# Main-v1_0.net
KiCad netlist of a schematic drawn in EAGLE
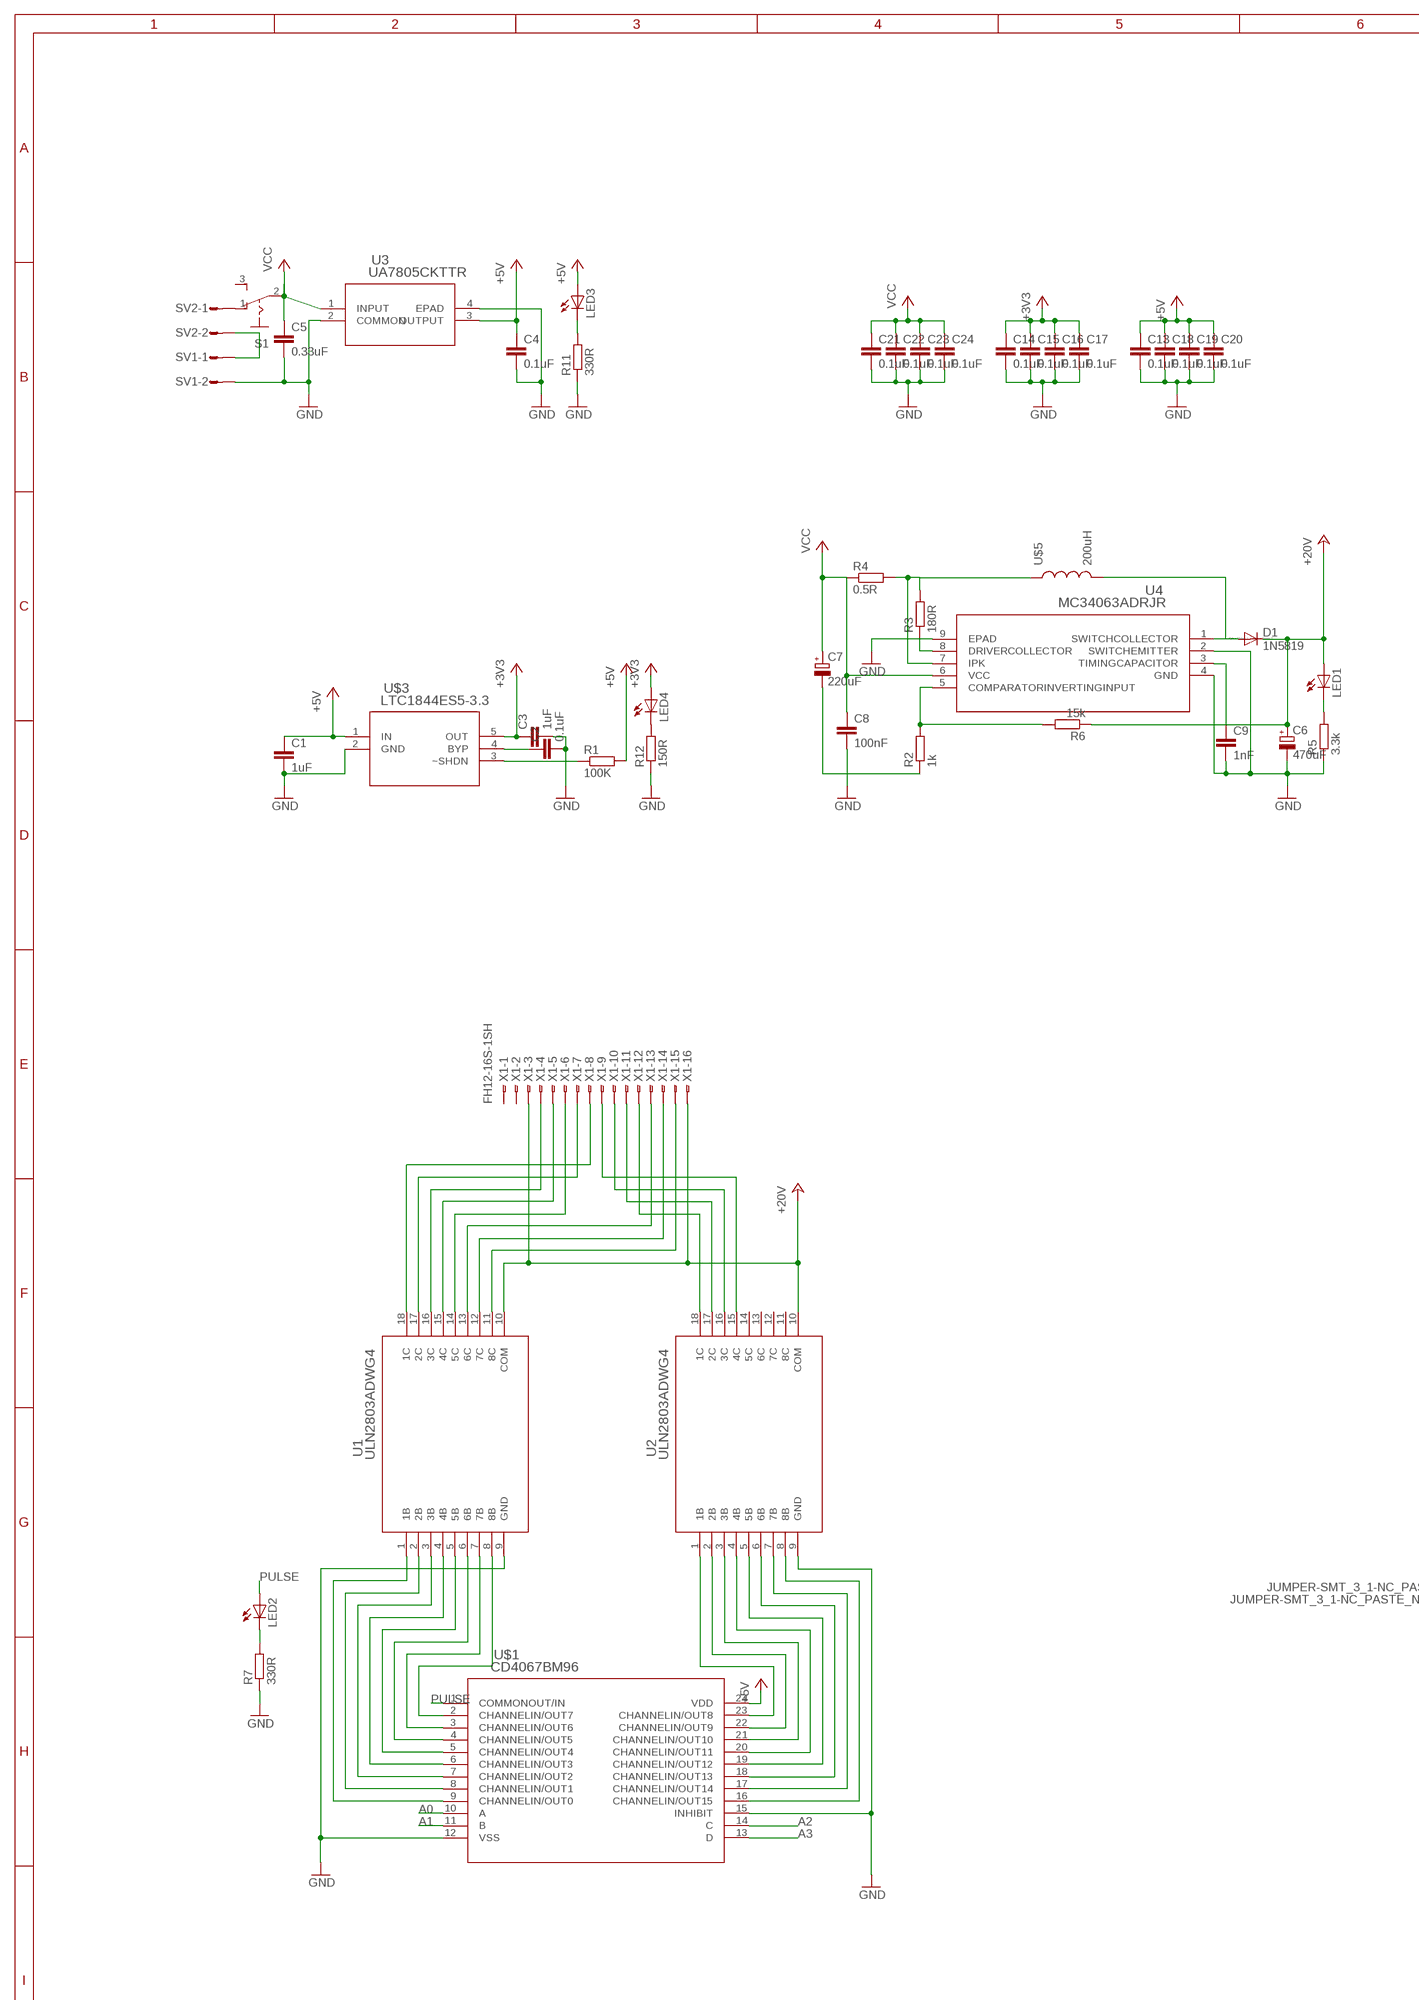
[diagram p0: schematic, sheet 1, part 1 of 2]
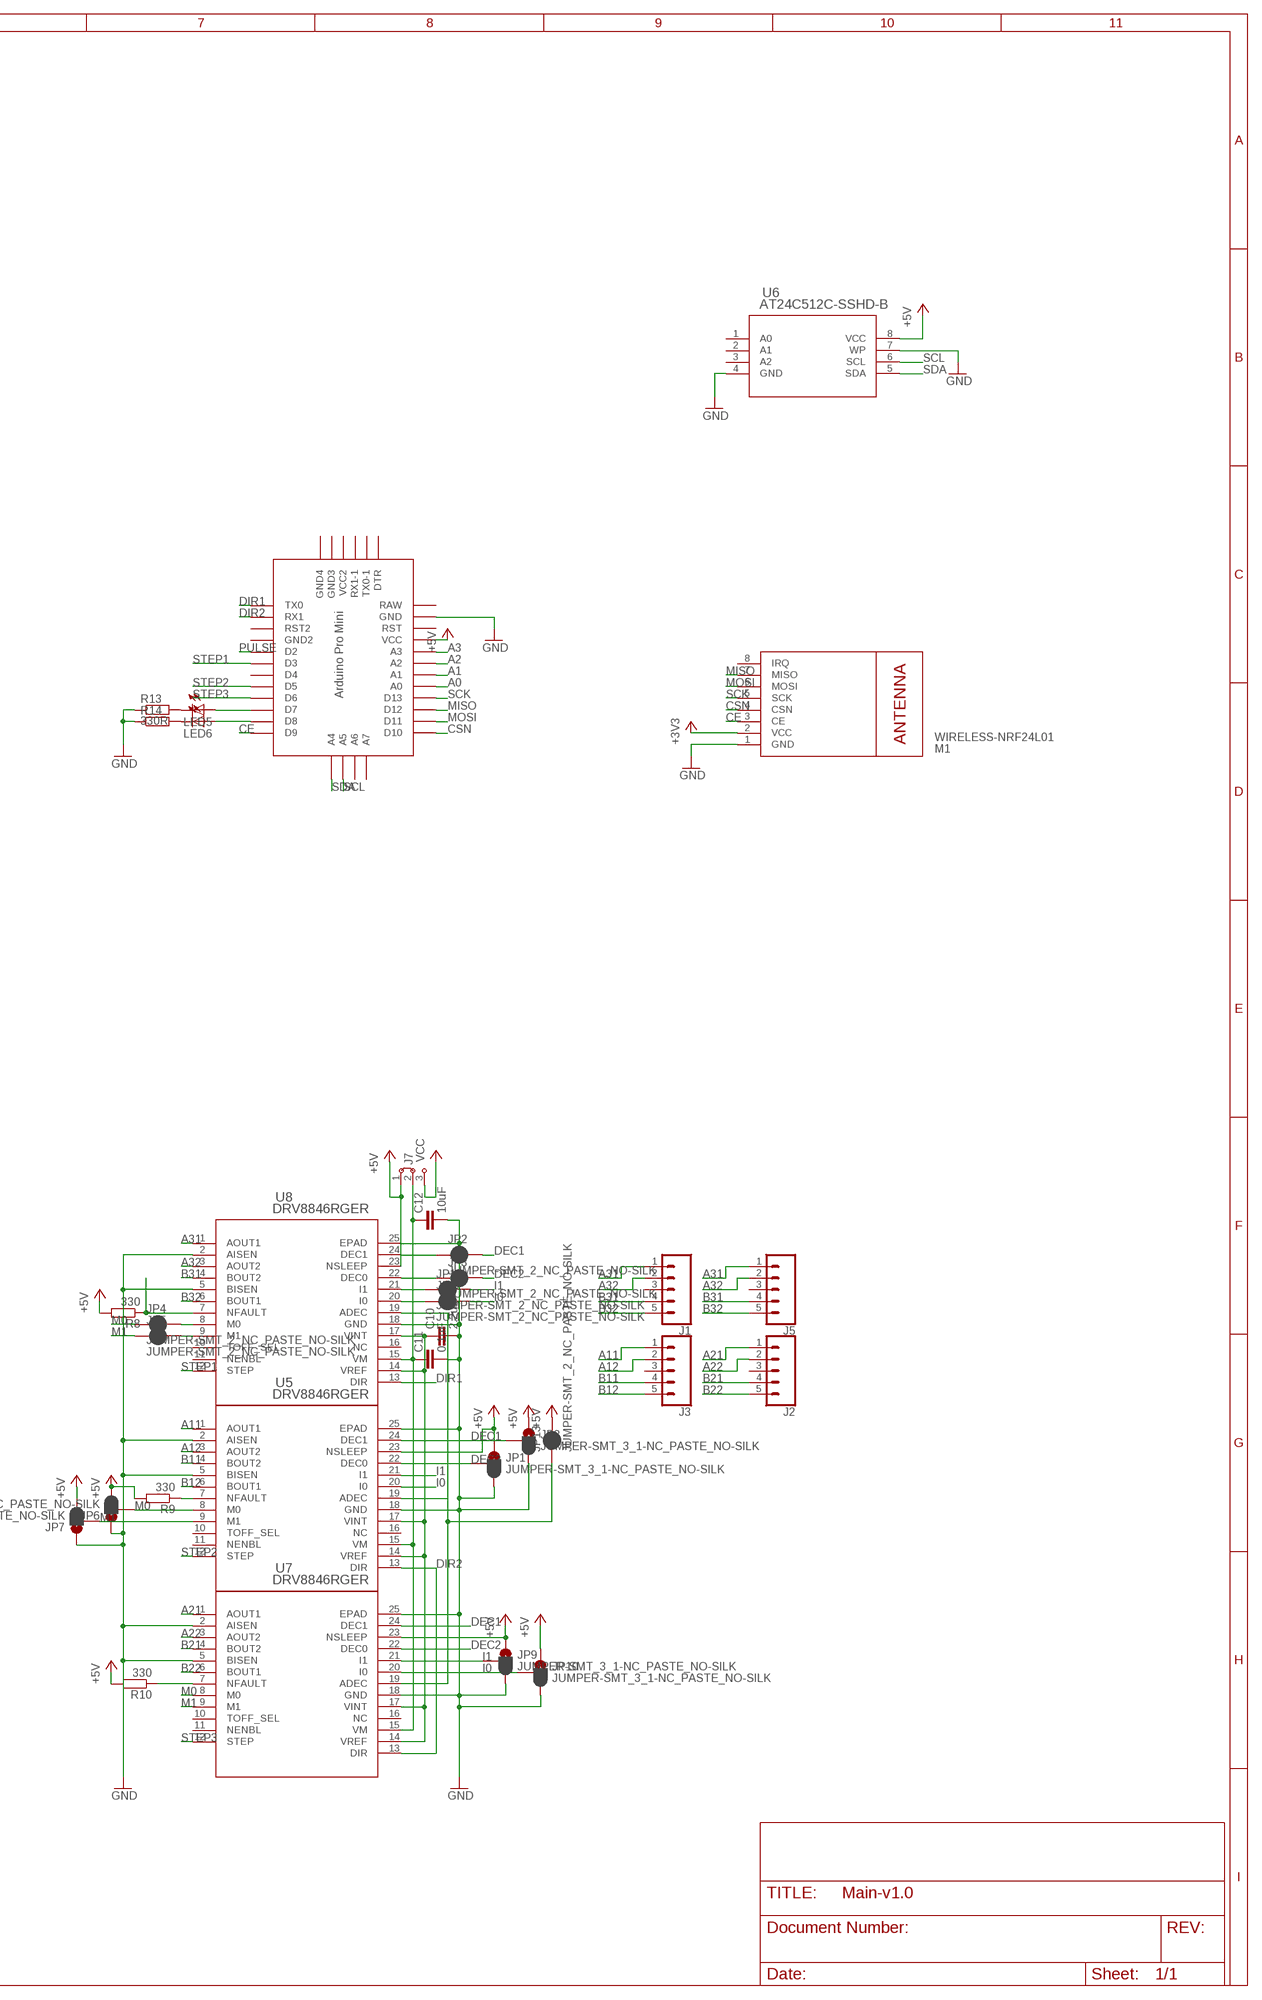
[diagram p1: schematic, sheet 1, part 2 of 2]

(export (version "E")
  (design (tool "Eeschema 10.0.6"))
  (components
    (comp (ref "C1")
      (value "1uF")
      (footprint "eagle-import:C0603")
      (libsource (lib "eagle-import") (part "resistor_C-EUC0603"))
    )
    (comp (ref "C2")
      (value "0.1uF")
      (footprint "eagle-import:C0603")
      (libsource (lib "eagle-import") (part "resistor_C-EUC0603"))
    )
    (comp (ref "C3")
      (value "1uF")
      (footprint "eagle-import:C0603")
      (libsource (lib "eagle-import") (part "resistor_C-EUC0603"))
    )
    (comp (ref "C4")
      (value "0.1uF")
      (footprint "eagle-import:C0603")
      (libsource (lib "eagle-import") (part "resistor_C-EUC0603"))
    )
    (comp (ref "C5")
      (value "0.33uF")
      (footprint "eagle-import:C0603")
      (libsource (lib "eagle-import") (part "resistor_C-EUC0603"))
    )
    (comp (ref "C6")
      (value "470uF")
      (footprint "eagle-import:153CLV-1010")
      (libsource (lib "eagle-import") (part "resistor_CPOL-EU153CLV-1010"))
    )
    (comp (ref "C7")
      (value "220uF")
      (footprint "eagle-import:SMC_C")
      (libsource (lib "eagle-import") (part "CPOL-EUSMCC"))
    )
    (comp (ref "C8")
      (value "100nF")
      (footprint "eagle-import:C0603")
      (libsource (lib "eagle-import") (part "C-EUC0603"))
    )
    (comp (ref "C9")
      (value "1nF")
      (footprint "eagle-import:C0603")
      (libsource (lib "eagle-import") (part "C-EUC0603"))
    )
    (comp (ref "C10")
      (value "2.2uF")
      (footprint "eagle-import:C0603")
      (libsource (lib "eagle-import") (part "resistor_348_C-EUC0603"))
    )
    (comp (ref "C11")
      (value "0.1uF")
      (footprint "eagle-import:C0603")
      (libsource (lib "eagle-import") (part "resistor_348_C-EUC0603"))
    )
    (comp (ref "C12")
      (value "10uF")
      (footprint "eagle-import:C0603")
      (libsource (lib "eagle-import") (part "resistor_348_C-EUC0603"))
    )
    (comp (ref "C13")
      (value "0.1uF")
      (footprint "eagle-import:C0603")
      (libsource (lib "eagle-import") (part "resistor_C-EUC0603"))
    )
    (comp (ref "C14")
      (value "0.1uF")
      (footprint "eagle-import:C0603")
      (libsource (lib "eagle-import") (part "resistor_C-EUC0603"))
    )
    (comp (ref "C15")
      (value "0.1uF")
      (footprint "eagle-import:C0603")
      (libsource (lib "eagle-import") (part "resistor_C-EUC0603"))
    )
    (comp (ref "C16")
      (value "0.1uF")
      (footprint "eagle-import:C0603")
      (libsource (lib "eagle-import") (part "resistor_C-EUC0603"))
    )
    (comp (ref "C17")
      (value "0.1uF")
      (footprint "eagle-import:C0603")
      (libsource (lib "eagle-import") (part "resistor_C-EUC0603"))
    )
    (comp (ref "C18")
      (value "0.1uF")
      (footprint "eagle-import:C0603")
      (libsource (lib "eagle-import") (part "resistor_C-EUC0603"))
    )
    (comp (ref "C19")
      (value "0.1uF")
      (footprint "eagle-import:C0603")
      (libsource (lib "eagle-import") (part "resistor_C-EUC0603"))
    )
    (comp (ref "C20")
      (value "0.1uF")
      (footprint "eagle-import:C0603")
      (libsource (lib "eagle-import") (part "resistor_C-EUC0603"))
    )
    (comp (ref "C21")
      (value "0.1uF")
      (footprint "eagle-import:C0603")
      (libsource (lib "eagle-import") (part "resistor_C-EUC0603"))
    )
    (comp (ref "C22")
      (value "0.1uF")
      (footprint "eagle-import:C0603")
      (libsource (lib "eagle-import") (part "resistor_C-EUC0603"))
    )
    (comp (ref "C23")
      (value "0.1uF")
      (footprint "eagle-import:C0603")
      (libsource (lib "eagle-import") (part "resistor_C-EUC0603"))
    )
    (comp (ref "C24")
      (value "0.1uF")
      (footprint "eagle-import:C0603")
      (libsource (lib "eagle-import") (part "resistor_C-EUC0603"))
    )
    (comp (ref "D1")
      (value "1N5819")
      (footprint "eagle-import:SOD123")
      (libsource (lib "eagle-import") (part "1N5819"))
    )
    (comp (ref "J1")
      (value "CONN_05JST-VERT")
      (footprint "eagle-import:JST-5-PTH-VERT")
      (libsource (lib "eagle-import") (part "CONN_05JST-VERT"))
    )
    (comp (ref "J2")
      (value "CONN_05JST-VERT")
      (footprint "eagle-import:JST-5-PTH-VERT")
      (libsource (lib "eagle-import") (part "CONN_05JST-VERT"))
    )
    (comp (ref "J3")
      (value "CONN_05JST-VERT")
      (footprint "eagle-import:JST-5-PTH-VERT")
      (libsource (lib "eagle-import") (part "CONN_05JST-VERT"))
    )
    (comp (ref "J5")
      (value "CONN_05JST-VERT")
      (footprint "eagle-import:JST-5-PTH-VERT")
      (libsource (lib "eagle-import") (part "CONN_05JST-VERT"))
    )
    (comp (ref "J7")
      (value "J2X2MM")
      (footprint "eagle-import:04C")
      (libsource (lib "eagle-import") (part "J2X2MM"))
    )
    (comp (ref "JP1")
      (value "JUMPER-SMT_3_1-NC_PASTE_NO-SILK")
      (footprint "eagle-import:SMT-JUMPER_3_1-NC_PASTE_NO-SILK")
      (libsource (lib "eagle-import") (part "JUMPER-SMT_3_1-NC_PASTE_NO-SILK"))
    )
    (comp (ref "JP2")
      (value "JUMPER-SMT_2_NC_PASTE_NO-SILK")
      (footprint "eagle-import:SMT-JUMPER_2_NC_PASTE_NO-SILK")
      (libsource (lib "eagle-import") (part "JUMPER-SMT_2_NC_PASTE_NO-SILK"))
    )
    (comp (ref "JP3")
      (value "JUMPER-SMT_2_NC_PASTE_NO-SILK")
      (footprint "eagle-import:SMT-JUMPER_2_NC_PASTE_NO-SILK")
      (libsource (lib "eagle-import") (part "JUMPER-SMT_2_NC_PASTE_NO-SILK"))
    )
    (comp (ref "JP4")
      (value "JUMPER-SMT_2_NC_PASTE_NO-SILK")
      (footprint "eagle-import:SMT-JUMPER_2_NC_PASTE_NO-SILK")
      (libsource (lib "eagle-import") (part "JUMPER-SMT_2_NC_PASTE_NO-SILK"))
    )
    (comp (ref "JP5")
      (value "JUMPER-SMT_2_NC_PASTE_NO-SILK")
      (footprint "eagle-import:SMT-JUMPER_2_NC_PASTE_NO-SILK")
      (libsource (lib "eagle-import") (part "JUMPER-SMT_2_NC_PASTE_NO-SILK"))
    )
    (comp (ref "JP6")
      (value "JUMPER-SMT_3_1-NC_PASTE_NO-SILK")
      (footprint "eagle-import:SMT-JUMPER_3_1-NC_PASTE_NO-SILK")
      (libsource (lib "eagle-import") (part "JUMPER-SMT_3_1-NC_PASTE_NO-SILK"))
    )
    (comp (ref "JP7")
      (value "JUMPER-SMT_3_1-NC_PASTE_NO-SILK")
      (footprint "eagle-import:SMT-JUMPER_3_1-NC_PASTE_NO-SILK")
      (libsource (lib "eagle-import") (part "JUMPER-SMT_3_1-NC_PASTE_NO-SILK"))
    )
    (comp (ref "JP8")
      (value "JUMPER-SMT_3_1-NC_PASTE_NO-SILK")
      (footprint "eagle-import:SMT-JUMPER_3_1-NC_PASTE_NO-SILK")
      (libsource (lib "eagle-import") (part "JUMPER-SMT_3_1-NC_PASTE_NO-SILK"))
    )
    (comp (ref "JP9")
      (value "JUMPER-SMT_3_1-NC_PASTE_NO-SILK")
      (footprint "eagle-import:SMT-JUMPER_3_1-NC_PASTE_NO-SILK")
      (libsource (lib "eagle-import") (part "JUMPER-SMT_3_1-NC_PASTE_NO-SILK"))
    )
    (comp (ref "JP10")
      (value "JUMPER-SMT_3_1-NC_PASTE_NO-SILK")
      (footprint "eagle-import:SMT-JUMPER_3_1-NC_PASTE_NO-SILK")
      (libsource (lib "eagle-import") (part "JUMPER-SMT_3_1-NC_PASTE_NO-SILK"))
    )
    (comp (ref "JP11")
      (value "JUMPER-SMT_2_NC_PASTE_NO-SILK")
      (footprint "eagle-import:SMT-JUMPER_2_NC_PASTE_NO-SILK")
      (libsource (lib "eagle-import") (part "JUMPER-SMT_2_NC_PASTE_NO-SILK"))
    )
    (comp (ref "JP12")
      (value "JUMPER-SMT_2_NC_PASTE_NO-SILK")
      (footprint "eagle-import:SMT-JUMPER_2_NC_PASTE_NO-SILK")
      (libsource (lib "eagle-import") (part "JUMPER-SMT_2_NC_PASTE_NO-SILK"))
    )
    (comp (ref "JP13")
      (value "JUMPER-SMT_2_NC_PASTE_NO-SILK")
      (footprint "eagle-import:SMT-JUMPER_2_NC_PASTE_NO-SILK")
      (libsource (lib "eagle-import") (part "JUMPER-SMT_2_NC_PASTE_NO-SILK"))
    )
    (comp (ref "LED1")
      (value "LEDSML0603")
      (footprint "eagle-import:SML0603")
      (libsource (lib "eagle-import") (part "LEDSML0603"))
    )
    (comp (ref "LED2")
      (value "LEDSML0603")
      (footprint "eagle-import:SML0603")
      (libsource (lib "eagle-import") (part "LEDSML0603"))
    )
    (comp (ref "LED3")
      (value "LEDSML0603")
      (footprint "eagle-import:SML0603")
      (libsource (lib "eagle-import") (part "LEDSML0603"))
    )
    (comp (ref "LED4")
      (value "LEDSML0603")
      (footprint "eagle-import:SML0603")
      (libsource (lib "eagle-import") (part "LEDSML0603"))
    )
    (comp (ref "LED5")
      (value "LEDSML0603")
      (footprint "eagle-import:SML0603")
      (libsource (lib "eagle-import") (part "LEDSML0603"))
    )
    (comp (ref "LED6")
      (value "LEDSML0603")
      (footprint "eagle-import:SML0603")
      (libsource (lib "eagle-import") (part "LEDSML0603"))
    )
    (comp (ref "M1")
      (value "WIRELESS-NRF24L01")
      (footprint "eagle-import:WIRELESS-NRF24L01")
      (libsource (lib "eagle-import") (part "WIRELESS-NRF24L01"))
    )
    (comp (ref "R1")
      (value "100K")
      (footprint "eagle-import:R0603")
      (libsource (lib "eagle-import") (part "R-EU_R0603"))
    )
    (comp (ref "R2")
      (value "1k")
      (footprint "eagle-import:R0603")
      (libsource (lib "eagle-import") (part "R-EU_R0603"))
    )
    (comp (ref "R3")
      (value "180R")
      (footprint "eagle-import:R0603")
      (libsource (lib "eagle-import") (part "R-EU_R0603"))
    )
    (comp (ref "R4")
      (value "0.5R")
      (footprint "eagle-import:R0603")
      (libsource (lib "eagle-import") (part "R-EU_R0603"))
    )
    (comp (ref "R5")
      (value "3.3k")
      (footprint "eagle-import:R0603")
      (libsource (lib "eagle-import") (part "R-EU_R0603"))
    )
    (comp (ref "R6")
      (value "15k")
      (footprint "eagle-import:R0603")
      (libsource (lib "eagle-import") (part "R-EU_R0603"))
    )
    (comp (ref "R7")
      (value "330R")
      (footprint "eagle-import:R0603")
      (libsource (lib "eagle-import") (part "R-EU_R0603"))
    )
    (comp (ref "R8")
      (value "330")
      (footprint "eagle-import:R0603")
      (libsource (lib "eagle-import") (part "R-EU_R0603"))
    )
    (comp (ref "R9")
      (value "330")
      (footprint "eagle-import:R0603")
      (libsource (lib "eagle-import") (part "R-EU_R0603"))
    )
    (comp (ref "R10")
      (value "330")
      (footprint "eagle-import:R0603")
      (libsource (lib "eagle-import") (part "R-EU_R0603"))
    )
    (comp (ref "R11")
      (value "330R")
      (footprint "eagle-import:R0603")
      (libsource (lib "eagle-import") (part "R-EU_R0603"))
    )
    (comp (ref "R12")
      (value "150R")
      (footprint "eagle-import:R0603")
      (libsource (lib "eagle-import") (part "R-EU_R0603"))
    )
    (comp (ref "R13")
      (value "330R")
      (footprint "eagle-import:R0603")
      (libsource (lib "eagle-import") (part "R-EU_R0603"))
    )
    (comp (ref "R14")
      (value "R-EU_R0603")
      (footprint "eagle-import:R0603")
      (libsource (lib "eagle-import") (part "R-EU_R0603"))
    )
    (comp (ref "S1")
      (value "255SB")
      (footprint "eagle-import:255SB")
      (libsource (lib "eagle-import") (part "255SB"))
    )
    (comp (ref "SV1")
      (value "L02P")
      (footprint "eagle-import:L02P")
      (libsource (lib "eagle-import") (part "L02P"))
    )
    (comp (ref "SV2")
      (value "L02P")
      (footprint "eagle-import:L02P")
      (libsource (lib "eagle-import") (part "L02P"))
    )
    (comp (ref "U$1")
      (value "CD4067BM96")
      (footprint "eagle-import:DW24")
      (fields (field (name "MANUFACTURER_PART_NUMBER") "CD4067B_DW_24"))
      (libsource (lib "eagle-import") (part "CD4067BM96"))
    )
    (comp (ref "U$2")
      (value "PRO-MINI")
      (footprint "eagle-import:PRO-MINI")
      (libsource (lib "eagle-import") (part "PRO-MINI"))
    )
    (comp (ref "U$3")
      (value "LTC1844ES5-3.3")
      (footprint "eagle-import:TSOT-23_S5")
      (libsource (lib "eagle-import") (part "LTC1844ES5-3.3"))
    )
    (comp (ref "U$5")
      (value "200uH")
      (footprint "eagle-import:CR54")
      (libsource (lib "eagle-import") (part "INDUCTORCR54"))
    )
    (comp (ref "U1")
      (value "ULN2803ADWG4")
      (footprint "eagle-import:DW18")
      (libsource (lib "eagle-import") (part "ULN2803ADWG4"))
    )
    (comp (ref "U2")
      (value "ULN2803ADWG4")
      (footprint "eagle-import:DW18")
      (libsource (lib "eagle-import") (part "ULN2803ADWG4"))
    )
    (comp (ref "U3")
      (value "UA7805CKTTR")
      (footprint "eagle-import:KTT3_6P22X6P6")
      (libsource (lib "eagle-import") (part "UA7805CKTTR"))
    )
    (comp (ref "U4")
      (value "MC34063ADRJR")
      (footprint "eagle-import:DRJ8_2P2X3")
      (libsource (lib "eagle-import") (part "MC34063ADRJR"))
    )
    (comp (ref "U5")
      (value "DRV8846RGER")
      (footprint "eagle-import:RGE24_2P45X2P45")
      (fields (field (name "MANUFACTURER_PART_NUMBER") "drv8846rger"))
      (libsource (lib "eagle-import") (part "DRV8846RGER"))
    )
    (comp (ref "U6")
      (value "AT24C512C-SSHD-B")
      (footprint "eagle-import:8S1")
      (fields (field (name "MANUFACTURER_PART_NUMBER") "AT24C512CSSHDB"))
      (libsource (lib "eagle-import") (part "AT24C512C-SSHD-B"))
    )
    (comp (ref "U7")
      (value "DRV8846RGER")
      (footprint "eagle-import:RGE24_2P45X2P45")
      (fields (field (name "MANUFACTURER_PART_NUMBER") "drv8846rger"))
      (libsource (lib "eagle-import") (part "DRV8846RGER"))
    )
    (comp (ref "U8")
      (value "DRV8846RGER")
      (footprint "eagle-import:RGE24_2P45X2P45")
      (fields (field (name "MANUFACTURER_PART_NUMBER") "drv8846rger"))
      (libsource (lib "eagle-import") (part "DRV8846RGER"))
    )
    (comp (ref "X1")
      (value "FH12-16S-1SH")
      (footprint "eagle-import:FH12-16S-1SH")
      (libsource (lib "eagle-import") (part "FH12-16S-1SH"))
    )
  )
  (nets
    (net (code "1") (name "+3V3") (class "Default")
      (node (ref "C14") (pin "1") (pinfunction "1_1") (pintype "passive"))
      (node (ref "C15") (pin "1") (pinfunction "1_1") (pintype "passive"))
      (node (ref "C16") (pin "1") (pinfunction "1_1") (pintype "passive"))
      (node (ref "C17") (pin "1") (pinfunction "1_1") (pintype "passive"))
      (node (ref "C3") (pin "1") (pinfunction "1_1") (pintype "passive"))
      (node (ref "LED4") (pin "A") (pinfunction "A_A") (pintype "passive"))
      (node (ref "M1") (pin "2") (pinfunction "VCC_2") (pintype "power_in"))
      (node (ref "U$3") (pin "5") (pinfunction "OUT_5") (pintype "passive"))
    )
    (net (code "2") (name "+5V") (class "Default")
      (node (ref "C1") (pin "1") (pinfunction "1_1") (pintype "passive"))
      (node (ref "C13") (pin "1") (pinfunction "1_1") (pintype "passive"))
      (node (ref "C18") (pin "1") (pinfunction "1_1") (pintype "passive"))
      (node (ref "C19") (pin "1") (pinfunction "1_1") (pintype "passive"))
      (node (ref "C20") (pin "1") (pinfunction "1_1") (pintype "passive"))
      (node (ref "C4") (pin "1") (pinfunction "1_1") (pintype "passive"))
      (node (ref "J7") (pin "1") (pinfunction "1_1") (pintype "passive"))
      (node (ref "JP1") (pin "1") (pinfunction "1_1") (pintype "passive"))
      (node (ref "JP10") (pin "1") (pinfunction "1_1") (pintype "passive"))
      (node (ref "JP13") (pin "2") (pinfunction "2_2") (pintype "passive"))
      (node (ref "JP6") (pin "3") (pinfunction "3_3") (pintype "passive"))
      (node (ref "JP7") (pin "3") (pinfunction "3_3") (pintype "passive"))
      (node (ref "JP8") (pin "1") (pinfunction "1_1") (pintype "passive"))
      (node (ref "JP9") (pin "1") (pinfunction "1_1") (pintype "passive"))
      (node (ref "LED3") (pin "A") (pinfunction "A_A") (pintype "passive"))
      (node (ref "R1") (pin "2") (pinfunction "2_2") (pintype "passive"))
      (node (ref "R10") (pin "2") (pinfunction "2_2") (pintype "passive"))
      (node (ref "R8") (pin "2") (pinfunction "2_2") (pintype "passive"))
      (node (ref "R9") (pin "2") (pinfunction "2_2") (pintype "passive"))
      (node (ref "U$1") (pin "24") (pinfunction "VDD_24") (pintype "power_in"))
      (node (ref "U$2") (pin "VCC") (pinfunction "VCC_VCC") (pintype "bidirectional"))
      (node (ref "U$3") (pin "1") (pinfunction "IN_1") (pintype "passive"))
      (node (ref "U3") (pin "3") (pinfunction "OUTPUT_3") (pintype "output"))
      (node (ref "U5") (pin "23") (pinfunction "NSLEEP_23") (pintype "input"))
      (node (ref "U6") (pin "8") (pinfunction "VCC_8") (pintype "power_in"))
      (node (ref "U7") (pin "23") (pinfunction "NSLEEP_23") (pintype "input"))
      (node (ref "U8") (pin "23") (pinfunction "NSLEEP_23") (pintype "input"))
    )
    (net (code "3") (name "+20V") (class "Default")
      (node (ref "C6") (pin "+") (pinfunction "+_+") (pintype "passive"))
      (node (ref "D1") (pin "C") (pinfunction "C_C") (pintype "passive"))
      (node (ref "LED1") (pin "A") (pinfunction "A_A") (pintype "passive"))
      (node (ref "R6") (pin "1") (pinfunction "1_1") (pintype "passive"))
      (node (ref "U1") (pin "10") (pinfunction "COM_10") (pintype "passive"))
      (node (ref "U2") (pin "10") (pinfunction "COM_10") (pintype "passive"))
      (node (ref "X1") (pin "16") (pinfunction "1_16") (pintype "passive"))
      (node (ref "X1") (pin "3") (pinfunction "1_3") (pintype "passive"))
    )
    (net (code "4") (name "/A0") (class "Default")
      (node (ref "U$1") (pin "10") (pinfunction "A_10") (pintype "passive"))
      (node (ref "U$2") (pin "A0") (pinfunction "A0_A0") (pintype "bidirectional"))
    )
    (net (code "5") (name "/A1") (class "Default")
      (node (ref "U$1") (pin "11") (pinfunction "B_11") (pintype "passive"))
      (node (ref "U$2") (pin "A1") (pinfunction "A1_A1") (pintype "bidirectional"))
    )
    (net (code "6") (name "/A2") (class "Default")
      (node (ref "U$1") (pin "14") (pinfunction "C_14") (pintype "passive"))
      (node (ref "U$2") (pin "A2") (pinfunction "A2_A2") (pintype "bidirectional"))
    )
    (net (code "7") (name "/A3") (class "Default")
      (node (ref "U$1") (pin "13") (pinfunction "D_13") (pintype "passive"))
      (node (ref "U$2") (pin "A3") (pinfunction "A3_A3") (pintype "bidirectional"))
    )
    (net (code "8") (name "/A11") (class "Default")
      (node (ref "J3") (pin "1") (pinfunction "1_1") (pintype "passive"))
      (node (ref "U5") (pin "1") (pinfunction "AOUT1_1") (pintype "output"))
    )
    (net (code "9") (name "/A12") (class "Default")
      (node (ref "J3") (pin "2") (pinfunction "2_2") (pintype "passive"))
      (node (ref "U5") (pin "3") (pinfunction "AOUT2_3") (pintype "output"))
    )
    (net (code "10") (name "/A21") (class "Default")
      (node (ref "J2") (pin "1") (pinfunction "1_1") (pintype "passive"))
      (node (ref "U7") (pin "1") (pinfunction "AOUT1_1") (pintype "output"))
    )
    (net (code "11") (name "/A22") (class "Default")
      (node (ref "J2") (pin "2") (pinfunction "2_2") (pintype "passive"))
      (node (ref "U7") (pin "3") (pinfunction "AOUT2_3") (pintype "output"))
    )
    (net (code "12") (name "/A31") (class "Default")
      (node (ref "J1") (pin "1") (pinfunction "1_1") (pintype "passive"))
      (node (ref "J5") (pin "1") (pinfunction "1_1") (pintype "passive"))
      (node (ref "U8") (pin "1") (pinfunction "AOUT1_1") (pintype "output"))
    )
    (net (code "13") (name "/A32") (class "Default")
      (node (ref "J1") (pin "2") (pinfunction "2_2") (pintype "passive"))
      (node (ref "J5") (pin "2") (pinfunction "2_2") (pintype "passive"))
      (node (ref "U8") (pin "3") (pinfunction "AOUT2_3") (pintype "output"))
    )
    (net (code "14") (name "/B11") (class "Default")
      (node (ref "J3") (pin "4") (pinfunction "4_4") (pintype "passive"))
      (node (ref "U5") (pin "4") (pinfunction "BOUT2_4") (pintype "output"))
    )
    (net (code "15") (name "/B12") (class "Default")
      (node (ref "J3") (pin "5") (pinfunction "5_5") (pintype "passive"))
      (node (ref "U5") (pin "6") (pinfunction "BOUT1_6") (pintype "output"))
    )
    (net (code "16") (name "/B21") (class "Default")
      (node (ref "J2") (pin "4") (pinfunction "4_4") (pintype "passive"))
      (node (ref "U7") (pin "4") (pinfunction "BOUT2_4") (pintype "output"))
    )
    (net (code "17") (name "/B22") (class "Default")
      (node (ref "J2") (pin "5") (pinfunction "5_5") (pintype "passive"))
      (node (ref "U7") (pin "6") (pinfunction "BOUT1_6") (pintype "output"))
    )
    (net (code "18") (name "/B31") (class "Default")
      (node (ref "J1") (pin "4") (pinfunction "4_4") (pintype "passive"))
      (node (ref "J5") (pin "4") (pinfunction "4_4") (pintype "passive"))
      (node (ref "U8") (pin "4") (pinfunction "BOUT2_4") (pintype "output"))
    )
    (net (code "19") (name "/B32") (class "Default")
      (node (ref "J1") (pin "5") (pinfunction "5_5") (pintype "passive"))
      (node (ref "J5") (pin "5") (pinfunction "5_5") (pintype "passive"))
      (node (ref "U8") (pin "6") (pinfunction "BOUT1_6") (pintype "output"))
    )
    (net (code "20") (name "/CE") (class "Default")
      (node (ref "M1") (pin "3") (pinfunction "CE_3") (pintype "bidirectional"))
      (node (ref "U$2") (pin "D9") (pinfunction "D9_D9") (pintype "bidirectional"))
    )
    (net (code "21") (name "/CSN") (class "Default")
      (node (ref "M1") (pin "4") (pinfunction "CSN_4") (pintype "bidirectional"))
      (node (ref "U$2") (pin "D10") (pinfunction "D10_D10") (pintype "bidirectional"))
    )
    (net (code "22") (name "/DEC1") (class "Default")
      (node (ref "JP2") (pin "2") (pinfunction "2_2") (pintype "passive"))
      (node (ref "JP8") (pin "2") (pinfunction "2_2") (pintype "passive"))
      (node (ref "U5") (pin "24") (pinfunction "DEC1_24") (pintype "input"))
      (node (ref "U7") (pin "24") (pinfunction "DEC1_24") (pintype "input"))
    )
    (net (code "23") (name "/DEC2") (class "Default")
      (node (ref "JP1") (pin "2") (pinfunction "2_2") (pintype "passive"))
      (node (ref "JP3") (pin "2") (pinfunction "2_2") (pintype "passive"))
      (node (ref "U5") (pin "22") (pinfunction "DEC0_22") (pintype "input"))
      (node (ref "U7") (pin "22") (pinfunction "DEC0_22") (pintype "input"))
    )
    (net (code "24") (name "/DIR1") (class "Default")
      (node (ref "U$2") (pin "TX0") (pinfunction "TX0_TX0") (pintype "bidirectional"))
      (node (ref "U8") (pin "13") (pinfunction "DIR_13") (pintype "input"))
    )
    (net (code "25") (name "/DIR2") (class "Default")
      (node (ref "U$2") (pin "RX1") (pinfunction "RX1_RX1") (pintype "bidirectional"))
      (node (ref "U5") (pin "13") (pinfunction "DIR_13") (pintype "input"))
      (node (ref "U7") (pin "13") (pinfunction "DIR_13") (pintype "input"))
    )
    (net (code "26") (name "/I0") (class "Default")
      (node (ref "JP10") (pin "2") (pinfunction "2_2") (pintype "passive"))
      (node (ref "JP12") (pin "2") (pinfunction "2_2") (pintype "passive"))
      (node (ref "U5") (pin "20") (pinfunction "I0_20") (pintype "input"))
      (node (ref "U7") (pin "20") (pinfunction "I0_20") (pintype "input"))
    )
    (net (code "27") (name "/I1") (class "Default")
      (node (ref "JP11") (pin "2") (pinfunction "2_2") (pintype "passive"))
      (node (ref "JP9") (pin "2") (pinfunction "2_2") (pintype "passive"))
      (node (ref "U5") (pin "21") (pinfunction "I1_21") (pintype "input"))
      (node (ref "U7") (pin "21") (pinfunction "I1_21") (pintype "input"))
    )
    (net (code "28") (name "/M0") (class "Default")
      (node (ref "JP4") (pin "1") (pinfunction "1_1") (pintype "passive"))
      (node (ref "JP6") (pin "2") (pinfunction "2_2") (pintype "passive"))
      (node (ref "U5") (pin "8") (pinfunction "M0_8") (pintype "input"))
      (node (ref "U7") (pin "8") (pinfunction "M0_8") (pintype "input"))
    )
    (net (code "29") (name "/M1") (class "Default")
      (node (ref "JP5") (pin "1") (pinfunction "1_1") (pintype "passive"))
      (node (ref "JP7") (pin "2") (pinfunction "2_2") (pintype "passive"))
      (node (ref "U5") (pin "9") (pinfunction "M1_9") (pintype "input"))
      (node (ref "U7") (pin "9") (pinfunction "M1_9") (pintype "input"))
    )
    (net (code "30") (name "/MISO") (class "Default")
      (node (ref "M1") (pin "7") (pinfunction "MISO_7") (pintype "bidirectional"))
      (node (ref "U$2") (pin "D12") (pinfunction "D12_D12") (pintype "bidirectional"))
    )
    (net (code "31") (name "/MOSI") (class "Default")
      (node (ref "M1") (pin "6") (pinfunction "MOSI_6") (pintype "bidirectional"))
      (node (ref "U$2") (pin "D11") (pinfunction "D11_D11") (pintype "bidirectional"))
    )
    (net (code "32") (name "/PULSE") (class "Default")
      (node (ref "LED2") (pin "A") (pinfunction "A_A") (pintype "passive"))
      (node (ref "U$1") (pin "1") (pinfunction "COMMONOUT/IN_1") (pintype "bidirectional"))
      (node (ref "U$2") (pin "D2") (pinfunction "D2_D2") (pintype "bidirectional"))
    )
    (net (code "33") (name "/RAW") (class "Default")
      (node (ref "U$2") (pin "RAW") (pinfunction "RAW_RAW") (pintype "power_in"))
    )
    (net (code "34") (name "/SCK") (class "Default")
      (node (ref "M1") (pin "5") (pinfunction "SCK_5") (pintype "bidirectional"))
      (node (ref "U$2") (pin "D13") (pinfunction "D13_D13") (pintype "bidirectional"))
    )
    (net (code "35") (name "/SCL") (class "Default")
      (node (ref "U$2") (pin "A5") (pinfunction "A5_A5") (pintype "bidirectional"))
      (node (ref "U6") (pin "6") (pinfunction "SCL_6") (pintype "input"))
    )
    (net (code "36") (name "/SDA") (class "Default")
      (node (ref "U$2") (pin "A4") (pinfunction "A4_A4") (pintype "bidirectional"))
      (node (ref "U6") (pin "5") (pinfunction "SDA_5") (pintype "passive"))
    )
    (net (code "37") (name "/STEP1") (class "Default")
      (node (ref "U$2") (pin "D3") (pinfunction "D3_D3") (pintype "bidirectional"))
      (node (ref "U8") (pin "12") (pinfunction "STEP_12") (pintype "input"))
    )
    (net (code "38") (name "/STEP2") (class "Default")
      (node (ref "U$2") (pin "D5") (pinfunction "D5_D5") (pintype "bidirectional"))
      (node (ref "U5") (pin "12") (pinfunction "STEP_12") (pintype "input"))
    )
    (net (code "39") (name "/STEP3") (class "Default")
      (node (ref "U$2") (pin "D6") (pinfunction "D6_D6") (pintype "bidirectional"))
      (node (ref "U7") (pin "12") (pinfunction "STEP_12") (pintype "input"))
    )
    (net (code "40") (name "GND") (class "Default")
      (node (ref "C1") (pin "2") (pinfunction "2_2") (pintype "passive"))
      (node (ref "C10") (pin "2") (pinfunction "2_2") (pintype "passive"))
      (node (ref "C11") (pin "2") (pinfunction "2_2") (pintype "passive"))
      (node (ref "C12") (pin "2") (pinfunction "2_2") (pintype "passive"))
      (node (ref "C13") (pin "2") (pinfunction "2_2") (pintype "passive"))
      (node (ref "C14") (pin "2") (pinfunction "2_2") (pintype "passive"))
      (node (ref "C15") (pin "2") (pinfunction "2_2") (pintype "passive"))
      (node (ref "C16") (pin "2") (pinfunction "2_2") (pintype "passive"))
      (node (ref "C17") (pin "2") (pinfunction "2_2") (pintype "passive"))
      (node (ref "C18") (pin "2") (pinfunction "2_2") (pintype "passive"))
      (node (ref "C19") (pin "2") (pinfunction "2_2") (pintype "passive"))
      (node (ref "C2") (pin "2") (pinfunction "2_2") (pintype "passive"))
      (node (ref "C20") (pin "2") (pinfunction "2_2") (pintype "passive"))
      (node (ref "C21") (pin "2") (pinfunction "2_2") (pintype "passive"))
      (node (ref "C22") (pin "2") (pinfunction "2_2") (pintype "passive"))
      (node (ref "C23") (pin "2") (pinfunction "2_2") (pintype "passive"))
      (node (ref "C24") (pin "2") (pinfunction "2_2") (pintype "passive"))
      (node (ref "C3") (pin "2") (pinfunction "2_2") (pintype "passive"))
      (node (ref "C4") (pin "2") (pinfunction "2_2") (pintype "passive"))
      (node (ref "C5") (pin "2") (pinfunction "2_2") (pintype "passive"))
      (node (ref "C6") (pin "-") (pinfunction "-_-") (pintype "passive"))
      (node (ref "C7") (pin "-") (pinfunction "-_-") (pintype "passive"))
      (node (ref "C8") (pin "2") (pinfunction "2_2") (pintype "passive"))
      (node (ref "C9") (pin "2") (pinfunction "2_2") (pintype "passive"))
      (node (ref "JP1") (pin "3") (pinfunction "3_3") (pintype "passive"))
      (node (ref "JP10") (pin "3") (pinfunction "3_3") (pintype "passive"))
      (node (ref "JP6") (pin "1") (pinfunction "1_1") (pintype "passive"))
      (node (ref "JP7") (pin "1") (pinfunction "1_1") (pintype "passive"))
      (node (ref "JP8") (pin "3") (pinfunction "3_3") (pintype "passive"))
      (node (ref "JP9") (pin "3") (pinfunction "3_3") (pintype "passive"))
      (node (ref "M1") (pin "1") (pinfunction "GND_1") (pintype "power_in"))
      (node (ref "R11") (pin "1") (pinfunction "1_1") (pintype "passive"))
      (node (ref "R12") (pin "1") (pinfunction "1_1") (pintype "passive"))
      (node (ref "R13") (pin "1") (pinfunction "1_1") (pintype "passive"))
      (node (ref "R14") (pin "1") (pinfunction "1_1") (pintype "passive"))
      (node (ref "R2") (pin "1") (pinfunction "1_1") (pintype "passive"))
      (node (ref "R5") (pin "1") (pinfunction "1_1") (pintype "passive"))
      (node (ref "R7") (pin "1") (pinfunction "1_1") (pintype "passive"))
      (node (ref "SV1") (pin "2") (pinfunction "S_2") (pintype "passive"))
      (node (ref "U$1") (pin "12") (pinfunction "VSS_12") (pintype "power_in"))
      (node (ref "U$1") (pin "15") (pinfunction "INHIBIT_15") (pintype "passive"))
      (node (ref "U$2") (pin "GND") (pinfunction "GND_GND") (pintype "input"))
      (node (ref "U$3") (pin "2") (pinfunction "GND_2") (pintype "passive"))
      (node (ref "U1") (pin "9") (pinfunction "GND_9") (pintype "passive"))
      (node (ref "U2") (pin "9") (pinfunction "GND_9") (pintype "passive"))
      (node (ref "U3") (pin "2") (pinfunction "COMMON_2") (pintype "power_in"))
      (node (ref "U3") (pin "4") (pinfunction "EPAD_4") (pintype "passive"))
      (node (ref "U4") (pin "2") (pinfunction "SWITCHEMITTER_2") (pintype "passive"))
      (node (ref "U4") (pin "4") (pinfunction "GND_4") (pintype "power_in"))
      (node (ref "U4") (pin "9") (pinfunction "EPAD_9") (pintype "power_in"))
      (node (ref "U5") (pin "18") (pinfunction "GND_18") (pintype "power_in"))
      (node (ref "U5") (pin "2") (pinfunction "AISEN_2") (pintype "output"))
      (node (ref "U5") (pin "25") (pinfunction "EPAD_25") (pintype "passive"))
      (node (ref "U5") (pin "5") (pinfunction "BISEN_5") (pintype "output"))
      (node (ref "U6") (pin "4") (pinfunction "GND_4") (pintype "power_in"))
      (node (ref "U6") (pin "7") (pinfunction "WP_7") (pintype "passive"))
      (node (ref "U7") (pin "18") (pinfunction "GND_18") (pintype "power_in"))
      (node (ref "U7") (pin "2") (pinfunction "AISEN_2") (pintype "output"))
      (node (ref "U7") (pin "25") (pinfunction "EPAD_25") (pintype "passive"))
      (node (ref "U7") (pin "5") (pinfunction "BISEN_5") (pintype "output"))
      (node (ref "U8") (pin "18") (pinfunction "GND_18") (pintype "power_in"))
      (node (ref "U8") (pin "2") (pinfunction "AISEN_2") (pintype "output"))
      (node (ref "U8") (pin "25") (pinfunction "EPAD_25") (pintype "passive"))
      (node (ref "U8") (pin "5") (pinfunction "BISEN_5") (pintype "output"))
    )
    (net (code "41") (name "Net-(LED1-PadC)") (class "Default")
      (node (ref "LED1") (pin "C") (pinfunction "C_C") (pintype "passive"))
      (node (ref "R5") (pin "2") (pinfunction "2_2") (pintype "passive"))
    )
    (net (code "42") (name "Net-(LED2-PadC)") (class "Default")
      (node (ref "LED2") (pin "C") (pinfunction "C_C") (pintype "passive"))
      (node (ref "R7") (pin "2") (pinfunction "2_2") (pintype "passive"))
    )
    (net (code "43") (name "Net-(LED3-PadC)") (class "Default")
      (node (ref "LED3") (pin "C") (pinfunction "C_C") (pintype "passive"))
      (node (ref "R11") (pin "2") (pinfunction "2_2") (pintype "passive"))
    )
    (net (code "44") (name "Net-(LED4-PadC)") (class "Default")
      (node (ref "LED4") (pin "C") (pinfunction "C_C") (pintype "passive"))
      (node (ref "R12") (pin "2") (pinfunction "2_2") (pintype "passive"))
    )
    (net (code "45") (name "Net-(LED5-PadA)") (class "Default")
      (node (ref "LED5") (pin "A") (pinfunction "A_A") (pintype "passive"))
      (node (ref "U$2") (pin "D7") (pinfunction "D7_D7") (pintype "bidirectional"))
    )
    (net (code "46") (name "Net-(LED5-PadC)") (class "Default")
      (node (ref "LED5") (pin "C") (pinfunction "C_C") (pintype "passive"))
      (node (ref "R13") (pin "2") (pinfunction "2_2") (pintype "passive"))
    )
    (net (code "47") (name "Net-(LED6-PadA)") (class "Default")
      (node (ref "LED6") (pin "A") (pinfunction "A_A") (pintype "passive"))
      (node (ref "U$2") (pin "D8") (pinfunction "D8_D8") (pintype "bidirectional"))
    )
    (net (code "48") (name "Net-(LED6-PadC)") (class "Default")
      (node (ref "LED6") (pin "C") (pinfunction "C_C") (pintype "passive"))
      (node (ref "R14") (pin "2") (pinfunction "2_2") (pintype "passive"))
    )
    (net (code "49") (name "Net-(S1-O)") (class "Default")
      (node (ref "S1") (pin "1") (pinfunction "O_1") (pintype "passive"))
      (node (ref "SV2") (pin "1") (pinfunction "S_1") (pintype "passive"))
    )
    (net (code "50") (name "Net-(SV1A-S)") (class "Default")
      (node (ref "SV1") (pin "1") (pinfunction "S_1") (pintype "passive"))
      (node (ref "SV2") (pin "2") (pinfunction "S_2") (pintype "passive"))
    )
    (net (code "51") (name "Net-(U$1-CHANNELIN{slash}OUT0)") (class "Default")
      (node (ref "U$1") (pin "9") (pinfunction "CHANNELIN/OUT0_9") (pintype "bidirectional"))
      (node (ref "U1") (pin "1") (pinfunction "1B_1") (pintype "passive"))
    )
    (net (code "52") (name "Net-(U$1-CHANNELIN{slash}OUT1)") (class "Default")
      (node (ref "U$1") (pin "8") (pinfunction "CHANNELIN/OUT1_8") (pintype "bidirectional"))
      (node (ref "U1") (pin "2") (pinfunction "2B_2") (pintype "passive"))
    )
    (net (code "53") (name "Net-(U$1-CHANNELIN{slash}OUT2)") (class "Default")
      (node (ref "U$1") (pin "7") (pinfunction "CHANNELIN/OUT2_7") (pintype "bidirectional"))
      (node (ref "U1") (pin "3") (pinfunction "3B_3") (pintype "passive"))
    )
    (net (code "54") (name "Net-(U$1-CHANNELIN{slash}OUT3)") (class "Default")
      (node (ref "U$1") (pin "6") (pinfunction "CHANNELIN/OUT3_6") (pintype "bidirectional"))
      (node (ref "U1") (pin "4") (pinfunction "4B_4") (pintype "passive"))
    )
    (net (code "55") (name "Net-(U$1-CHANNELIN{slash}OUT4)") (class "Default")
      (node (ref "U$1") (pin "5") (pinfunction "CHANNELIN/OUT4_5") (pintype "bidirectional"))
      (node (ref "U1") (pin "5") (pinfunction "5B_5") (pintype "passive"))
    )
    (net (code "56") (name "Net-(U$1-CHANNELIN{slash}OUT5)") (class "Default")
      (node (ref "U$1") (pin "4") (pinfunction "CHANNELIN/OUT5_4") (pintype "bidirectional"))
      (node (ref "U1") (pin "6") (pinfunction "6B_6") (pintype "passive"))
    )
    (net (code "57") (name "Net-(U$1-CHANNELIN{slash}OUT6)") (class "Default")
      (node (ref "U$1") (pin "3") (pinfunction "CHANNELIN/OUT6_3") (pintype "bidirectional"))
      (node (ref "U1") (pin "7") (pinfunction "7B_7") (pintype "passive"))
    )
    (net (code "58") (name "Net-(U$1-CHANNELIN{slash}OUT7)") (class "Default")
      (node (ref "U$1") (pin "2") (pinfunction "CHANNELIN/OUT7_2") (pintype "bidirectional"))
      (node (ref "U1") (pin "8") (pinfunction "8B_8") (pintype "passive"))
    )
    (net (code "59") (name "Net-(U$1-CHANNELIN{slash}OUT8)") (class "Default")
      (node (ref "U$1") (pin "23") (pinfunction "CHANNELIN/OUT8_23") (pintype "bidirectional"))
      (node (ref "U2") (pin "1") (pinfunction "1B_1") (pintype "passive"))
    )
    (net (code "60") (name "Net-(U$1-CHANNELIN{slash}OUT9)") (class "Default")
      (node (ref "U$1") (pin "22") (pinfunction "CHANNELIN/OUT9_22") (pintype "bidirectional"))
      (node (ref "U2") (pin "2") (pinfunction "2B_2") (pintype "passive"))
    )
    (net (code "61") (name "Net-(U$1-CHANNELIN{slash}OUT10)") (class "Default")
      (node (ref "U$1") (pin "21") (pinfunction "CHANNELIN/OUT10_21") (pintype "bidirectional"))
      (node (ref "U2") (pin "3") (pinfunction "3B_3") (pintype "passive"))
    )
    (net (code "62") (name "Net-(U$1-CHANNELIN{slash}OUT11)") (class "Default")
      (node (ref "U$1") (pin "20") (pinfunction "CHANNELIN/OUT11_20") (pintype "bidirectional"))
      (node (ref "U2") (pin "4") (pinfunction "4B_4") (pintype "passive"))
    )
    (net (code "63") (name "Net-(U$1-CHANNELIN{slash}OUT12)") (class "Default")
      (node (ref "U$1") (pin "19") (pinfunction "CHANNELIN/OUT12_19") (pintype "bidirectional"))
      (node (ref "U2") (pin "5") (pinfunction "5B_5") (pintype "passive"))
    )
    (net (code "64") (name "Net-(U$1-CHANNELIN{slash}OUT13)") (class "Default")
      (node (ref "U$1") (pin "18") (pinfunction "CHANNELIN/OUT13_18") (pintype "bidirectional"))
      (node (ref "U2") (pin "6") (pinfunction "6B_6") (pintype "passive"))
    )
    (net (code "65") (name "Net-(U$1-CHANNELIN{slash}OUT14)") (class "Default")
      (node (ref "U$1") (pin "17") (pinfunction "CHANNELIN/OUT14_17") (pintype "bidirectional"))
      (node (ref "U2") (pin "7") (pinfunction "7B_7") (pintype "passive"))
    )
    (net (code "66") (name "Net-(U$1-CHANNELIN{slash}OUT15)") (class "Default")
      (node (ref "U$1") (pin "16") (pinfunction "CHANNELIN/OUT15_16") (pintype "bidirectional"))
      (node (ref "U2") (pin "8") (pinfunction "8B_8") (pintype "passive"))
    )
    (net (code "67") (name "Net-(U$3-BYP)") (class "Default")
      (node (ref "C2") (pin "1") (pinfunction "1_1") (pintype "passive"))
      (node (ref "U$3") (pin "4") (pinfunction "BYP_4") (pintype "passive"))
    )
    (net (code "68") (name "Net-(U$3-~{SHDN})") (class "Default")
      (node (ref "R1") (pin "1") (pinfunction "1_1") (pintype "passive"))
      (node (ref "U$3") (pin "3") (pinfunction "~{SHDN}_3") (pintype "passive"))
    )
    (net (code "69") (name "Net-(U$5-1)") (class "Default")
      (node (ref "R3") (pin "2") (pinfunction "2_2") (pintype "passive"))
      (node (ref "R4") (pin "2") (pinfunction "2_2") (pintype "passive"))
      (node (ref "U$5") (pin "P$1") (pinfunction "1_P$1") (pintype "passive"))
      (node (ref "U4") (pin "7") (pinfunction "IPK_7") (pintype "passive"))
    )
    (net (code "70") (name "Net-(U$5-2)") (class "Default")
      (node (ref "D1") (pin "A") (pinfunction "A_A") (pintype "passive"))
      (node (ref "U$5") (pin "P$2") (pinfunction "2_P$2") (pintype "passive"))
      (node (ref "U4") (pin "1") (pinfunction "SWITCHCOLLECTOR_1") (pintype "passive"))
    )
    (net (code "71") (name "Net-(U1-1C)") (class "Default")
      (node (ref "U1") (pin "18") (pinfunction "1C_18") (pintype "passive"))
      (node (ref "X1") (pin "8") (pinfunction "1_8") (pintype "passive"))
    )
    (net (code "72") (name "Net-(U1-2C)") (class "Default")
      (node (ref "U1") (pin "17") (pinfunction "2C_17") (pintype "passive"))
      (node (ref "X1") (pin "7") (pinfunction "1_7") (pintype "passive"))
    )
    (net (code "73") (name "Net-(U1-3C)") (class "Default")
      (node (ref "U1") (pin "16") (pinfunction "3C_16") (pintype "passive"))
      (node (ref "X1") (pin "4") (pinfunction "1_4") (pintype "passive"))
    )
    (net (code "74") (name "Net-(U1-4C)") (class "Default")
      (node (ref "U1") (pin "15") (pinfunction "4C_15") (pintype "passive"))
      (node (ref "X1") (pin "5") (pinfunction "1_5") (pintype "passive"))
    )
    (net (code "75") (name "Net-(U1-5C)") (class "Default")
      (node (ref "U1") (pin "14") (pinfunction "5C_14") (pintype "passive"))
      (node (ref "X1") (pin "6") (pinfunction "1_6") (pintype "passive"))
    )
    (net (code "76") (name "Net-(U1-6C)") (class "Default")
      (node (ref "U1") (pin "13") (pinfunction "6C_13") (pintype "passive"))
      (node (ref "X1") (pin "13") (pinfunction "1_13") (pintype "passive"))
    )
    (net (code "77") (name "Net-(U1-7C)") (class "Default")
      (node (ref "U1") (pin "12") (pinfunction "7C_12") (pintype "passive"))
      (node (ref "X1") (pin "14") (pinfunction "1_14") (pintype "passive"))
    )
    (net (code "78") (name "Net-(U1-8C)") (class "Default")
      (node (ref "U1") (pin "11") (pinfunction "8C_11") (pintype "passive"))
      (node (ref "X1") (pin "15") (pinfunction "1_15") (pintype "passive"))
    )
    (net (code "79") (name "Net-(U2-1C)") (class "Default")
      (node (ref "U2") (pin "18") (pinfunction "1C_18") (pintype "passive"))
      (node (ref "X1") (pin "12") (pinfunction "1_12") (pintype "passive"))
    )
    (net (code "80") (name "Net-(U2-2C)") (class "Default")
      (node (ref "U2") (pin "17") (pinfunction "2C_17") (pintype "passive"))
      (node (ref "X1") (pin "11") (pinfunction "1_11") (pintype "passive"))
    )
    (net (code "81") (name "Net-(U2-3C)") (class "Default")
      (node (ref "U2") (pin "16") (pinfunction "3C_16") (pintype "passive"))
      (node (ref "X1") (pin "10") (pinfunction "1_10") (pintype "passive"))
    )
    (net (code "82") (name "Net-(U2-4C)") (class "Default")
      (node (ref "U2") (pin "15") (pinfunction "4C_15") (pintype "passive"))
      (node (ref "X1") (pin "9") (pinfunction "1_9") (pintype "passive"))
    )
    (net (code "83") (name "Net-(U4-COMPARATORINVERTINGINPUT)") (class "Default")
      (node (ref "R2") (pin "2") (pinfunction "2_2") (pintype "passive"))
      (node (ref "R6") (pin "2") (pinfunction "2_2") (pintype "passive"))
      (node (ref "U4") (pin "5") (pinfunction "COMPARATORINVERTINGINPUT_5") (pintype "passive"))
    )
    (net (code "84") (name "Net-(U4-DRIVERCOLLECTOR)") (class "Default")
      (node (ref "R3") (pin "1") (pinfunction "1_1") (pintype "passive"))
      (node (ref "U4") (pin "8") (pinfunction "DRIVERCOLLECTOR_8") (pintype "passive"))
    )
    (net (code "85") (name "Net-(U4-TIMINGCAPACITOR)") (class "Default")
      (node (ref "C9") (pin "1") (pinfunction "1_1") (pintype "passive"))
      (node (ref "U4") (pin "3") (pinfunction "TIMINGCAPACITOR_3") (pintype "passive"))
    )
    (net (code "86") (name "Net-(U5-ADEC)") (class "Default")
      (node (ref "JP13") (pin "1") (pinfunction "1_1") (pintype "passive"))
      (node (ref "U5") (pin "19") (pinfunction "ADEC_19") (pintype "input"))
      (node (ref "U7") (pin "19") (pinfunction "ADEC_19") (pintype "input"))
      (node (ref "U8") (pin "19") (pinfunction "ADEC_19") (pintype "input"))
    )
    (net (code "87") (name "Net-(U5-NFAULT)") (class "Default")
      (node (ref "R9") (pin "1") (pinfunction "1_1") (pintype "passive"))
      (node (ref "U5") (pin "7") (pinfunction "NFAULT_7") (pintype "output"))
    )
    (net (code "88") (name "Net-(U5-VINT)") (class "Default")
      (node (ref "C10") (pin "1") (pinfunction "1_1") (pintype "passive"))
      (node (ref "U5") (pin "14") (pinfunction "VREF_14") (pintype "input"))
      (node (ref "U5") (pin "17") (pinfunction "VINT_17") (pintype "passive"))
      (node (ref "U7") (pin "14") (pinfunction "VREF_14") (pintype "input"))
      (node (ref "U7") (pin "17") (pinfunction "VINT_17") (pintype "passive"))
      (node (ref "U8") (pin "14") (pinfunction "VREF_14") (pintype "input"))
      (node (ref "U8") (pin "17") (pinfunction "VINT_17") (pintype "passive"))
    )
    (net (code "89") (name "Net-(U5-VM)") (class "Default")
      (node (ref "C11") (pin "1") (pinfunction "1_1") (pintype "passive"))
      (node (ref "C12") (pin "1") (pinfunction "1_1") (pintype "passive"))
      (node (ref "J7") (pin "2") (pinfunction "2_2") (pintype "passive"))
      (node (ref "U5") (pin "15") (pinfunction "VM_15") (pintype "power_in"))
      (node (ref "U7") (pin "15") (pinfunction "VM_15") (pintype "power_in"))
      (node (ref "U8") (pin "15") (pinfunction "VM_15") (pintype "power_in"))
    )
    (net (code "90") (name "Net-(U7-NFAULT)") (class "Default")
      (node (ref "R10") (pin "1") (pinfunction "1_1") (pintype "passive"))
      (node (ref "U7") (pin "7") (pinfunction "NFAULT_7") (pintype "output"))
    )
    (net (code "91") (name "Net-(U8-DEC0)") (class "Default")
      (node (ref "JP3") (pin "1") (pinfunction "1_1") (pintype "passive"))
      (node (ref "U8") (pin "22") (pinfunction "DEC0_22") (pintype "input"))
    )
    (net (code "92") (name "Net-(U8-DEC1)") (class "Default")
      (node (ref "JP2") (pin "1") (pinfunction "1_1") (pintype "passive"))
      (node (ref "U8") (pin "24") (pinfunction "DEC1_24") (pintype "input"))
    )
    (net (code "93") (name "Net-(U8-I0)") (class "Default")
      (node (ref "JP12") (pin "1") (pinfunction "1_1") (pintype "passive"))
      (node (ref "U8") (pin "20") (pinfunction "I0_20") (pintype "input"))
    )
    (net (code "94") (name "Net-(U8-I1)") (class "Default")
      (node (ref "JP11") (pin "1") (pinfunction "1_1") (pintype "passive"))
      (node (ref "U8") (pin "21") (pinfunction "I1_21") (pintype "input"))
    )
    (net (code "95") (name "Net-(U8-M0)") (class "Default")
      (node (ref "JP4") (pin "2") (pinfunction "2_2") (pintype "passive"))
      (node (ref "U8") (pin "8") (pinfunction "M0_8") (pintype "input"))
    )
    (net (code "96") (name "Net-(U8-M1)") (class "Default")
      (node (ref "JP5") (pin "2") (pinfunction "2_2") (pintype "passive"))
      (node (ref "U8") (pin "9") (pinfunction "M1_9") (pintype "input"))
    )
    (net (code "97") (name "Net-(U8-NFAULT)") (class "Default")
      (node (ref "R8") (pin "1") (pinfunction "1_1") (pintype "passive"))
      (node (ref "U8") (pin "7") (pinfunction "NFAULT_7") (pintype "output"))
    )
    (net (code "98") (name "VCC") (class "Default")
      (node (ref "C21") (pin "1") (pinfunction "1_1") (pintype "passive"))
      (node (ref "C22") (pin "1") (pinfunction "1_1") (pintype "passive"))
      (node (ref "C23") (pin "1") (pinfunction "1_1") (pintype "passive"))
      (node (ref "C24") (pin "1") (pinfunction "1_1") (pintype "passive"))
      (node (ref "C5") (pin "1") (pinfunction "1_1") (pintype "passive"))
      (node (ref "C7") (pin "+") (pinfunction "+_+") (pintype "passive"))
      (node (ref "C8") (pin "1") (pinfunction "1_1") (pintype "passive"))
      (node (ref "J7") (pin "3") (pinfunction "3_3") (pintype "passive"))
      (node (ref "R4") (pin "1") (pinfunction "1_1") (pintype "passive"))
      (node (ref "S1") (pin "2") (pinfunction "P_2") (pintype "passive"))
      (node (ref "U3") (pin "1") (pinfunction "INPUT_1") (pintype "input"))
      (node (ref "U4") (pin "6") (pinfunction "VCC_6") (pintype "power_in"))
    )
    (net (code "99") (name "unconnected-(J1-Pad3)") (class "Default")
      (node (ref "J1") (pin "3") (pinfunction "3_3") (pintype "passive"))
    )
    (net (code "100") (name "unconnected-(J2-Pad3)") (class "Default")
      (node (ref "J2") (pin "3") (pinfunction "3_3") (pintype "passive"))
    )
    (net (code "101") (name "unconnected-(J3-Pad3)") (class "Default")
      (node (ref "J3") (pin "3") (pinfunction "3_3") (pintype "passive"))
    )
    (net (code "102") (name "unconnected-(J5-Pad3)") (class "Default")
      (node (ref "J5") (pin "3") (pinfunction "3_3") (pintype "passive"))
    )
    (net (code "103") (name "unconnected-(M1-IRQ-Pad8)") (class "Default")
      (node (ref "M1") (pin "8") (pinfunction "IRQ_8") (pintype "bidirectional"))
    )
    (net (code "104") (name "unconnected-(S1-S-Pad3)") (class "Default")
      (node (ref "S1") (pin "3") (pinfunction "S_3") (pintype "passive"))
    )
    (net (code "105") (name "unconnected-(U$2-GND2-PadGND1)") (class "Default")
      (node (ref "U$2") (pin "GND1") (pinfunction "GND2_GND1") (pintype "bidirectional"))
    )
    (net (code "106") (name "unconnected-(U$2-GND4-PadGND2)") (class "Default")
      (node (ref "U$2") (pin "GND2") (pinfunction "GND4_GND2") (pintype "bidirectional"))
    )
    (net (code "107") (name "unconnected-(U$2-PadA6)") (class "Default")
      (node (ref "U$2") (pin "A6") (pinfunction "A6_A6") (pintype "bidirectional"))
    )
    (net (code "108") (name "unconnected-(U$2-PadA7)") (class "Default")
      (node (ref "U$2") (pin "A7") (pinfunction "A7_A7") (pintype "bidirectional"))
    )
    (net (code "109") (name "unconnected-(U$2-PadD4)") (class "Default")
      (node (ref "U$2") (pin "D4") (pinfunction "D4_D4") (pintype "bidirectional"))
    )
    (net (code "110") (name "unconnected-(U$2-PadDTR)") (class "Default")
      (node (ref "U$2") (pin "DTR") (pinfunction "DTR_DTR") (pintype "bidirectional"))
    )
    (net (code "111") (name "unconnected-(U$2-PadGND3)") (class "Default")
      (node (ref "U$2") (pin "GND3") (pinfunction "GND3_GND3") (pintype "bidirectional"))
    )
    (net (code "112") (name "unconnected-(U$2-PadRST)") (class "Default")
      (node (ref "U$2") (pin "RST") (pinfunction "RST_RST") (pintype "bidirectional"))
    )
    (net (code "113") (name "unconnected-(U$2-PadRX1-1)") (class "Default")
      (node (ref "U$2") (pin "RX1-1") (pinfunction "RX1-1_RX1-1") (pintype "bidirectional"))
    )
    (net (code "114") (name "unconnected-(U$2-PadTX0-1)") (class "Default")
      (node (ref "U$2") (pin "TX0-1") (pinfunction "TX0-1_TX0-1") (pintype "bidirectional"))
    )
    (net (code "115") (name "unconnected-(U$2-RST2-PadRST1)") (class "Default")
      (node (ref "U$2") (pin "RST1") (pinfunction "RST2_RST1") (pintype "bidirectional"))
    )
    (net (code "116") (name "unconnected-(U$2-VCC2-PadVCC1)") (class "Default")
      (node (ref "U$2") (pin "VCC1") (pinfunction "VCC2_VCC1") (pintype "bidirectional"))
    )
    (net (code "117") (name "unconnected-(U2-5C-Pad14)") (class "Default")
      (node (ref "U2") (pin "14") (pinfunction "5C_14") (pintype "passive"))
    )
    (net (code "118") (name "unconnected-(U2-6C-Pad13)") (class "Default")
      (node (ref "U2") (pin "13") (pinfunction "6C_13") (pintype "passive"))
    )
    (net (code "119") (name "unconnected-(U2-7C-Pad12)") (class "Default")
      (node (ref "U2") (pin "12") (pinfunction "7C_12") (pintype "passive"))
    )
    (net (code "120") (name "unconnected-(U2-8C-Pad11)") (class "Default")
      (node (ref "U2") (pin "11") (pinfunction "8C_11") (pintype "passive"))
    )
    (net (code "121") (name "unconnected-(U5-NC-Pad16)") (class "Default")
      (node (ref "U5") (pin "16") (pinfunction "NC_16") (pintype "no_connect"))
    )
    (net (code "122") (name "unconnected-(U5-NENBL-Pad11)") (class "Default")
      (node (ref "U5") (pin "11") (pinfunction "NENBL_11") (pintype "input"))
    )
    (net (code "123") (name "unconnected-(U5-TOFF_SEL-Pad10)") (class "Default")
      (node (ref "U5") (pin "10") (pinfunction "TOFF_SEL_10") (pintype "input"))
    )
    (net (code "124") (name "unconnected-(U6-A0-Pad1)") (class "Default")
      (node (ref "U6") (pin "1") (pinfunction "A0_1") (pintype "input"))
    )
    (net (code "125") (name "unconnected-(U6-A1-Pad2)") (class "Default")
      (node (ref "U6") (pin "2") (pinfunction "A1_2") (pintype "input"))
    )
    (net (code "126") (name "unconnected-(U6-A2-Pad3)") (class "Default")
      (node (ref "U6") (pin "3") (pinfunction "A2_3") (pintype "input"))
    )
    (net (code "127") (name "unconnected-(U7-NC-Pad16)") (class "Default")
      (node (ref "U7") (pin "16") (pinfunction "NC_16") (pintype "no_connect"))
    )
    (net (code "128") (name "unconnected-(U7-NENBL-Pad11)") (class "Default")
      (node (ref "U7") (pin "11") (pinfunction "NENBL_11") (pintype "input"))
    )
    (net (code "129") (name "unconnected-(U7-TOFF_SEL-Pad10)") (class "Default")
      (node (ref "U7") (pin "10") (pinfunction "TOFF_SEL_10") (pintype "input"))
    )
    (net (code "130") (name "unconnected-(U8-NC-Pad16)") (class "Default")
      (node (ref "U8") (pin "16") (pinfunction "NC_16") (pintype "no_connect"))
    )
    (net (code "131") (name "unconnected-(U8-NENBL-Pad11)") (class "Default")
      (node (ref "U8") (pin "11") (pinfunction "NENBL_11") (pintype "input"))
    )
    (net (code "132") (name "unconnected-(U8-TOFF_SEL-Pad10)") (class "Default")
      (node (ref "U8") (pin "10") (pinfunction "TOFF_SEL_10") (pintype "input"))
    )
    (net (code "133") (name "unconnected-(X1-Pad1)") (class "Default")
      (node (ref "X1") (pin "1") (pinfunction "1_1") (pintype "passive"))
    )
    (net (code "134") (name "unconnected-(X1I-1-Pad2)") (class "Default")
      (node (ref "X1") (pin "2") (pinfunction "1_2") (pintype "passive"))
    )
  )
)
